# BreakoutBoardAFE4404-THROUGH.net
KiCad netlist of a schematic drawn in EAGLE
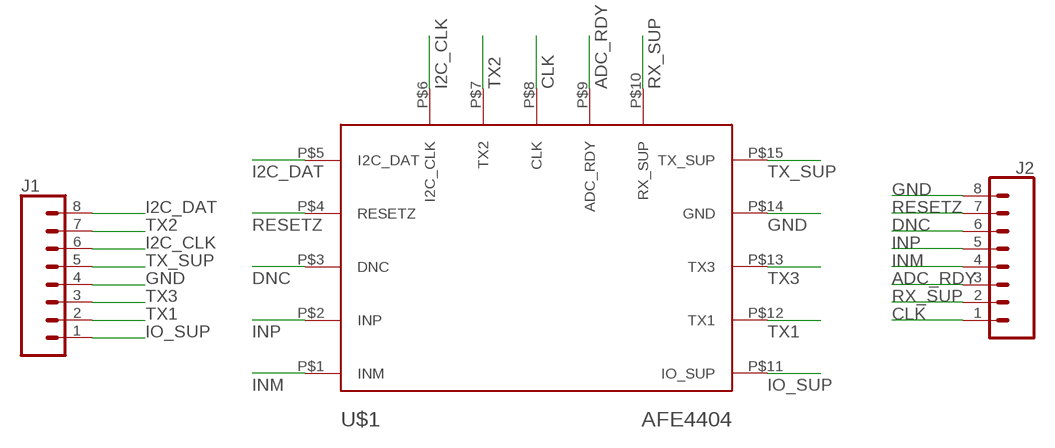
[diagram p0: schematic, sheet 1]

(export (version "E")
  (design (tool "Eeschema 10.0.6"))
  (components
    (comp (ref "J1")
      (value "CONN_08\"")
      (footprint "eagle-import:1X08")
      (libsource (lib "eagle-import") (part "CONN_08{dblquote}"))
    )
    (comp (ref "J2")
      (value "CONN_08\"")
      (footprint "eagle-import:1X08")
      (libsource (lib "eagle-import") (part "CONN_08{dblquote}"))
    )
    (comp (ref "U$1")
      (value "AFE4404")
      (footprint "eagle-import:AFE4404-THROUGH")
      (libsource (lib "eagle-import") (part "AFE4404"))
    )
  )
  (nets
    (net (code "1") (name "/ADC_RDY") (class "Default")
      (node (ref "J2") (pin "3") (pinfunction "3_3") (pintype "passive"))
      (node (ref "U$1") (pin "P$9") (pinfunction "ADC_RDY_P$9") (pintype "bidirectional"))
    )
    (net (code "2") (name "/CLK") (class "Default")
      (node (ref "J2") (pin "1") (pinfunction "1_1") (pintype "passive"))
      (node (ref "U$1") (pin "P$8") (pinfunction "CLK_P$8") (pintype "bidirectional"))
    )
    (net (code "3") (name "/DNC") (class "Default")
      (node (ref "J2") (pin "6") (pinfunction "6_6") (pintype "passive"))
      (node (ref "U$1") (pin "P$3") (pinfunction "DNC_P$3") (pintype "bidirectional"))
    )
    (net (code "4") (name "/GND") (class "Default")
      (node (ref "J1") (pin "4") (pinfunction "4_4") (pintype "passive"))
      (node (ref "J2") (pin "8") (pinfunction "8_8") (pintype "passive"))
      (node (ref "U$1") (pin "P$14") (pinfunction "GND_P$14") (pintype "bidirectional"))
    )
    (net (code "5") (name "/I2C_CLK") (class "Default")
      (node (ref "J1") (pin "6") (pinfunction "6_6") (pintype "passive"))
      (node (ref "U$1") (pin "P$6") (pinfunction "I2C_CLK_P$6") (pintype "bidirectional"))
    )
    (net (code "6") (name "/I2C_DAT") (class "Default")
      (node (ref "J1") (pin "8") (pinfunction "8_8") (pintype "passive"))
      (node (ref "U$1") (pin "P$5") (pinfunction "I2C_DAT_P$5") (pintype "bidirectional"))
    )
    (net (code "7") (name "/INM") (class "Default")
      (node (ref "J2") (pin "4") (pinfunction "4_4") (pintype "passive"))
      (node (ref "U$1") (pin "P$1") (pinfunction "INM_P$1") (pintype "bidirectional"))
    )
    (net (code "8") (name "/INP") (class "Default")
      (node (ref "J2") (pin "5") (pinfunction "5_5") (pintype "passive"))
      (node (ref "U$1") (pin "P$2") (pinfunction "INP_P$2") (pintype "bidirectional"))
    )
    (net (code "9") (name "/IO_SUP") (class "Default")
      (node (ref "J1") (pin "1") (pinfunction "1_1") (pintype "passive"))
      (node (ref "U$1") (pin "P$11") (pinfunction "IO_SUP_P$11") (pintype "bidirectional"))
    )
    (net (code "10") (name "/RESETZ") (class "Default")
      (node (ref "J2") (pin "7") (pinfunction "7_7") (pintype "passive"))
      (node (ref "U$1") (pin "P$4") (pinfunction "RESETZ_P$4") (pintype "bidirectional"))
    )
    (net (code "11") (name "/RX_SUP") (class "Default")
      (node (ref "J2") (pin "2") (pinfunction "2_2") (pintype "passive"))
      (node (ref "U$1") (pin "P$10") (pinfunction "RX_SUP_P$10") (pintype "bidirectional"))
    )
    (net (code "12") (name "/TX1") (class "Default")
      (node (ref "J1") (pin "2") (pinfunction "2_2") (pintype "passive"))
      (node (ref "U$1") (pin "P$12") (pinfunction "TX1_P$12") (pintype "bidirectional"))
    )
    (net (code "13") (name "/TX2") (class "Default")
      (node (ref "J1") (pin "7") (pinfunction "7_7") (pintype "passive"))
      (node (ref "U$1") (pin "P$7") (pinfunction "TX2_P$7") (pintype "bidirectional"))
    )
    (net (code "14") (name "/TX3") (class "Default")
      (node (ref "J1") (pin "3") (pinfunction "3_3") (pintype "passive"))
      (node (ref "U$1") (pin "P$13") (pinfunction "TX3_P$13") (pintype "bidirectional"))
    )
    (net (code "15") (name "/TX_SUP") (class "Default")
      (node (ref "J1") (pin "5") (pinfunction "5_5") (pintype "passive"))
      (node (ref "U$1") (pin "P$15") (pinfunction "TX_SUP_P$15") (pintype "bidirectional"))
    )
  )
)
